# MUX_Adapter.net
KiCad netlist of a schematic drawn in EAGLE
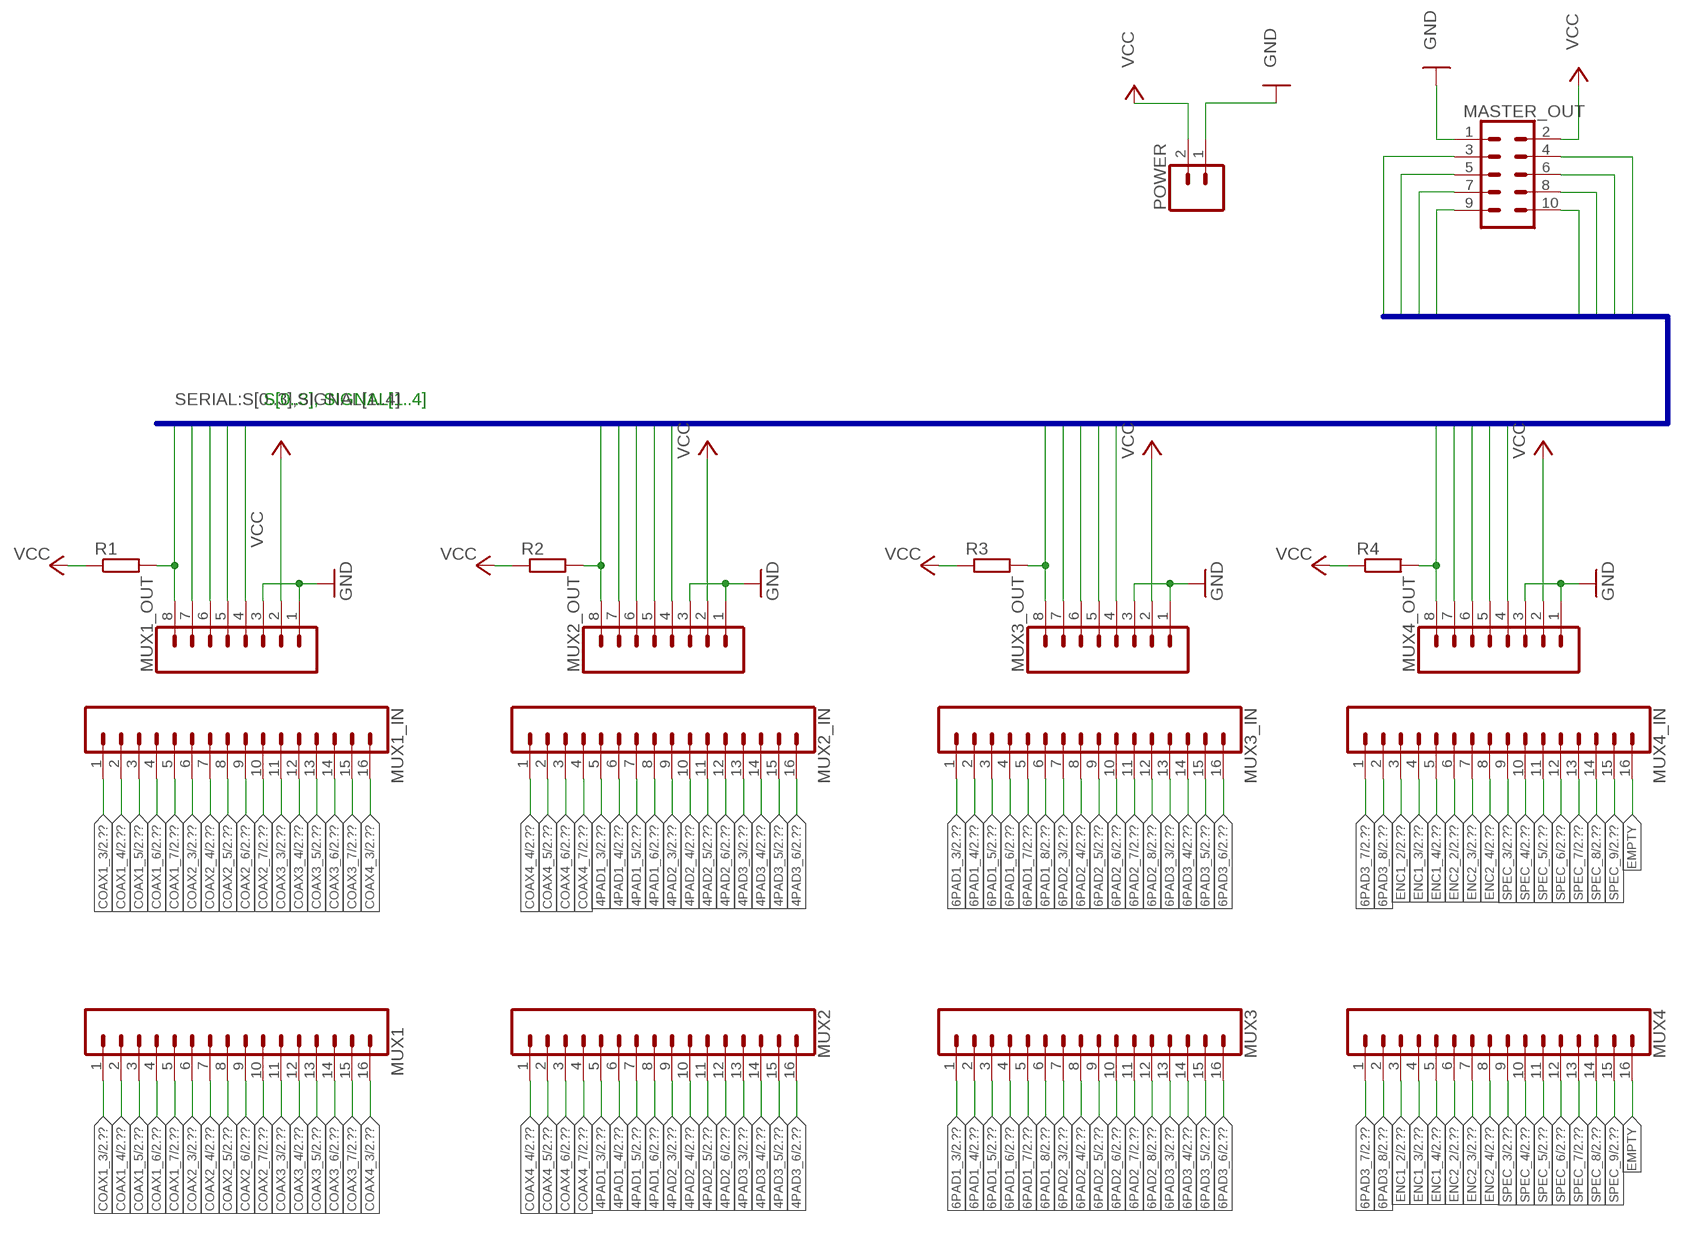
[diagram p0: schematic, sheet 1]
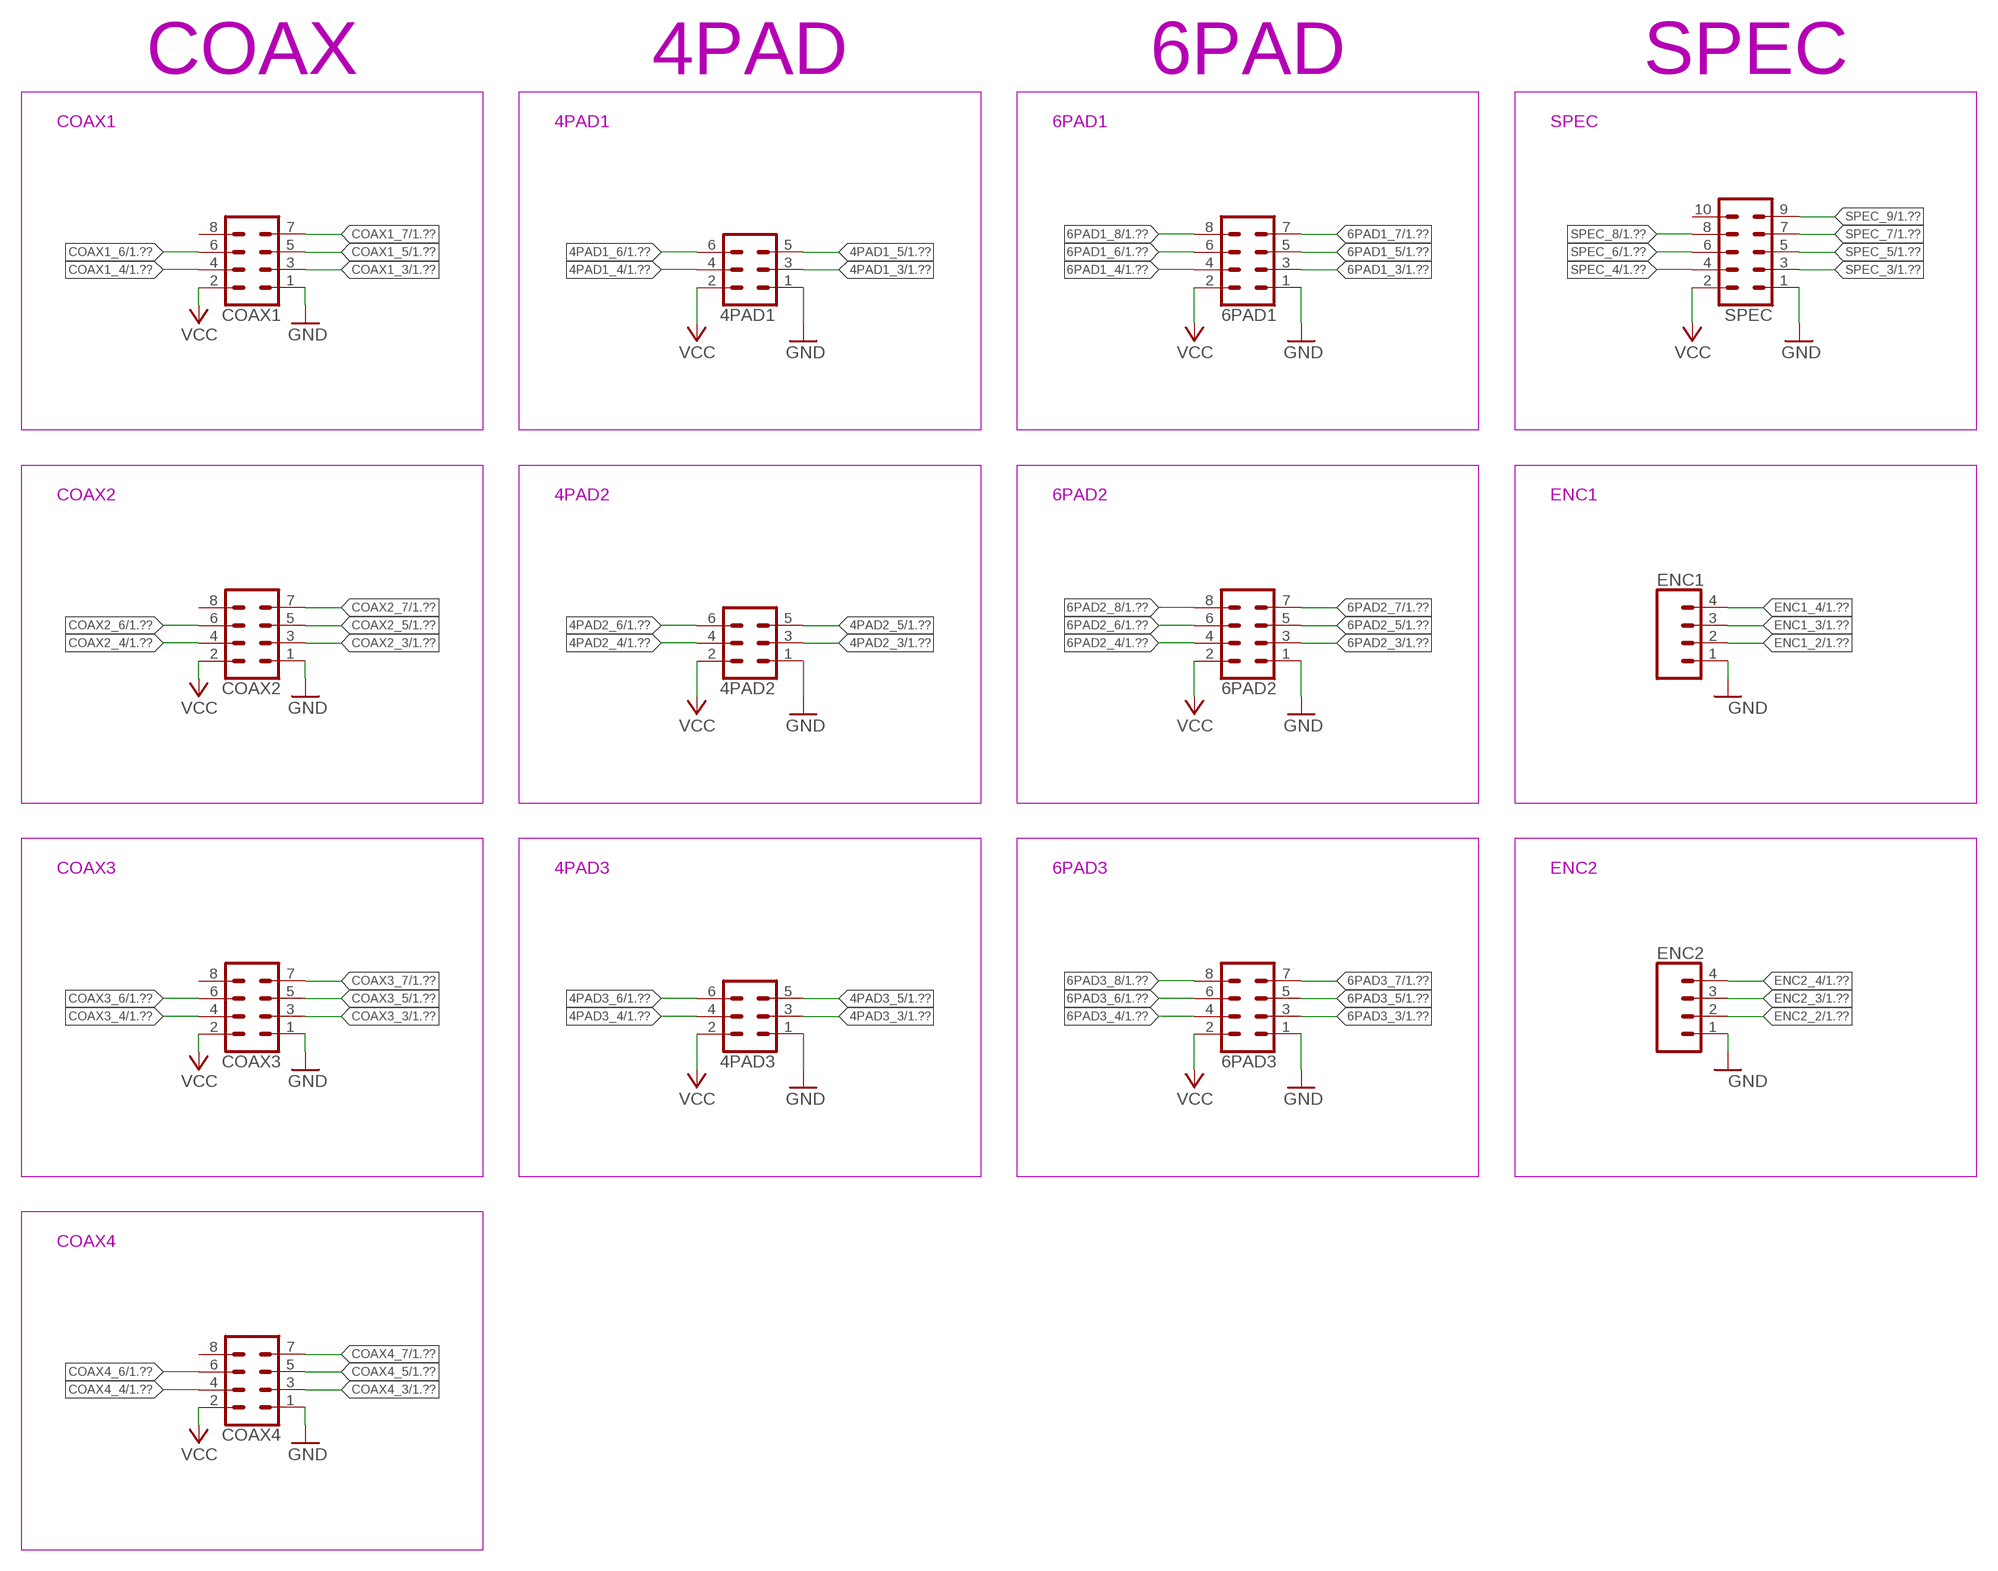
[diagram p1: schematic, sheet 2]

(export (version "E")
  (design (tool "Eeschema 10.0.6"))
  (components
    (comp (ref "4PAD1")
      (value "CONN_03X2NO_SILK")
      (footprint "eagle-import:2X3-NS")
      (libsource (lib "eagle-import") (part "CONN_03X2NO_SILK"))
    )
    (comp (ref "4PAD2")
      (value "CONN_03X2NO_SILK")
      (footprint "eagle-import:2X3-NS")
      (libsource (lib "eagle-import") (part "CONN_03X2NO_SILK"))
    )
    (comp (ref "4PAD3")
      (value "CONN_03X2NO_SILK")
      (footprint "eagle-import:2X3-NS")
      (libsource (lib "eagle-import") (part "CONN_03X2NO_SILK"))
    )
    (comp (ref "6PAD1")
      (value "CONN_04X2")
      (footprint "eagle-import:2X4")
      (libsource (lib "eagle-import") (part "CONN_04X2"))
    )
    (comp (ref "6PAD2")
      (value "CONN_04X2")
      (footprint "eagle-import:2X4")
      (libsource (lib "eagle-import") (part "CONN_04X2"))
    )
    (comp (ref "6PAD3")
      (value "CONN_04X2")
      (footprint "eagle-import:2X4")
      (libsource (lib "eagle-import") (part "CONN_04X2"))
    )
    (comp (ref "COAX1")
      (value "CONN_04X2")
      (footprint "eagle-import:2X4")
      (libsource (lib "eagle-import") (part "CONN_04X2"))
    )
    (comp (ref "COAX2")
      (value "CONN_04X2")
      (footprint "eagle-import:2X4")
      (libsource (lib "eagle-import") (part "CONN_04X2"))
    )
    (comp (ref "COAX3")
      (value "CONN_04X2")
      (footprint "eagle-import:2X4")
      (libsource (lib "eagle-import") (part "CONN_04X2"))
    )
    (comp (ref "COAX4")
      (value "CONN_04X2")
      (footprint "eagle-import:2X4")
      (libsource (lib "eagle-import") (part "CONN_04X2"))
    )
    (comp (ref "ENC1")
      (value "CONN_04PTH")
      (footprint "eagle-import:1X04")
      (libsource (lib "eagle-import") (part "CONN_04PTH"))
    )
    (comp (ref "ENC2")
      (value "CONN_04PTH")
      (footprint "eagle-import:1X04")
      (libsource (lib "eagle-import") (part "CONN_04PTH"))
    )
    (comp (ref "SPEC")
      (value "CONN_05X2PTH")
      (footprint "eagle-import:2X5")
      (libsource (lib "eagle-import") (part "CONN_05X2PTH"))
    )
    (comp (ref "MASTER_OUT")
      (value "CONN_05X2SHD-NS")
      (footprint "eagle-import:2X5-SHROUDED-NS")
      (libsource (lib "eagle-import") (part "CONN_05X2SHD-NS"))
    )
    (comp (ref "MUX1")
      (value "CONN_16")
      (footprint "eagle-import:1X16")
      (libsource (lib "eagle-import") (part "CONN_16"))
    )
    (comp (ref "MUX1_IN")
      (value "CONN_16")
      (footprint "eagle-import:1X16")
      (libsource (lib "eagle-import") (part "CONN_16"))
    )
    (comp (ref "MUX1_OUT")
      (value "CONN_08\"")
      (footprint "eagle-import:1X08")
      (libsource (lib "eagle-import") (part "CONN_08{dblquote}"))
    )
    (comp (ref "MUX2")
      (value "CONN_16")
      (footprint "eagle-import:1X16")
      (libsource (lib "eagle-import") (part "CONN_16"))
    )
    (comp (ref "MUX2_IN")
      (value "CONN_16")
      (footprint "eagle-import:1X16")
      (libsource (lib "eagle-import") (part "CONN_16"))
    )
    (comp (ref "MUX2_OUT")
      (value "CONN_08\"")
      (footprint "eagle-import:1X08")
      (libsource (lib "eagle-import") (part "CONN_08{dblquote}"))
    )
    (comp (ref "MUX3")
      (value "CONN_16")
      (footprint "eagle-import:1X16")
      (libsource (lib "eagle-import") (part "CONN_16"))
    )
    (comp (ref "MUX3_IN")
      (value "CONN_16")
      (footprint "eagle-import:1X16")
      (libsource (lib "eagle-import") (part "CONN_16"))
    )
    (comp (ref "MUX3_OUT")
      (value "CONN_08\"")
      (footprint "eagle-import:1X08")
      (libsource (lib "eagle-import") (part "CONN_08{dblquote}"))
    )
    (comp (ref "MUX4")
      (value "CONN_16")
      (footprint "eagle-import:1X16")
      (libsource (lib "eagle-import") (part "CONN_16"))
    )
    (comp (ref "MUX4_IN")
      (value "CONN_16")
      (footprint "eagle-import:1X16")
      (libsource (lib "eagle-import") (part "CONN_16"))
    )
    (comp (ref "MUX4_OUT")
      (value "CONN_08\"")
      (footprint "eagle-import:1X08")
      (libsource (lib "eagle-import") (part "CONN_08{dblquote}"))
    )
    (comp (ref "POWER")
      (value "CONN_02")
      (footprint "eagle-import:1X02")
      (libsource (lib "eagle-import") (part "CONN_02"))
    )
    (comp (ref "R1")
      (value "R-EU_0207/10")
      (footprint "eagle-import:0207_10")
      (libsource (lib "eagle-import") (part "R-EU_0207/10"))
    )
    (comp (ref "R2")
      (value "R-EU_0207/10")
      (footprint "eagle-import:0207_10")
      (libsource (lib "eagle-import") (part "R-EU_0207/10"))
    )
    (comp (ref "R3")
      (value "R-EU_0207/10")
      (footprint "eagle-import:0207_10")
      (libsource (lib "eagle-import") (part "R-EU_0207/10"))
    )
    (comp (ref "R4")
      (value "R-EU_0207/10")
      (footprint "eagle-import:0207_10")
      (libsource (lib "eagle-import") (part "R-EU_0207/10"))
    )
  )
  (nets
    (net (code "2") (name "4PAD1_3") (class "Default")
      (node (ref "4PAD1") (pin "3") (pinfunction "3_3") (pintype "bidirectional"))
      (node (ref "MUX2") (pin "5") (pinfunction "5_5") (pintype "passive"))
      (node (ref "MUX2_IN") (pin "5") (pinfunction "5_5") (pintype "passive"))
    )
    (net (code "3") (name "4PAD1_4") (class "Default")
      (node (ref "4PAD1") (pin "4") (pinfunction "4_4") (pintype "bidirectional"))
      (node (ref "MUX2") (pin "6") (pinfunction "6_6") (pintype "passive"))
      (node (ref "MUX2_IN") (pin "6") (pinfunction "6_6") (pintype "passive"))
    )
    (net (code "4") (name "4PAD1_5") (class "Default")
      (node (ref "4PAD1") (pin "5") (pinfunction "5_5") (pintype "bidirectional"))
      (node (ref "MUX2") (pin "7") (pinfunction "7_7") (pintype "passive"))
      (node (ref "MUX2_IN") (pin "7") (pinfunction "7_7") (pintype "passive"))
    )
    (net (code "5") (name "4PAD1_6") (class "Default")
      (node (ref "4PAD1") (pin "6") (pinfunction "6_6") (pintype "bidirectional"))
      (node (ref "MUX2") (pin "8") (pinfunction "8_8") (pintype "passive"))
      (node (ref "MUX2_IN") (pin "8") (pinfunction "8_8") (pintype "passive"))
    )
    (net (code "6") (name "4PAD2_3") (class "Default")
      (node (ref "4PAD2") (pin "3") (pinfunction "3_3") (pintype "bidirectional"))
      (node (ref "MUX2") (pin "9") (pinfunction "9_9") (pintype "passive"))
      (node (ref "MUX2_IN") (pin "9") (pinfunction "9_9") (pintype "passive"))
    )
    (net (code "7") (name "4PAD2_4") (class "Default")
      (node (ref "4PAD2") (pin "4") (pinfunction "4_4") (pintype "bidirectional"))
      (node (ref "MUX2") (pin "10") (pinfunction "10_10") (pintype "passive"))
      (node (ref "MUX2_IN") (pin "10") (pinfunction "10_10") (pintype "passive"))
    )
    (net (code "8") (name "4PAD2_5") (class "Default")
      (node (ref "4PAD2") (pin "5") (pinfunction "5_5") (pintype "bidirectional"))
      (node (ref "MUX2") (pin "11") (pinfunction "11_11") (pintype "passive"))
      (node (ref "MUX2_IN") (pin "11") (pinfunction "11_11") (pintype "passive"))
    )
    (net (code "9") (name "4PAD2_6") (class "Default")
      (node (ref "4PAD2") (pin "6") (pinfunction "6_6") (pintype "bidirectional"))
      (node (ref "MUX2") (pin "12") (pinfunction "12_12") (pintype "passive"))
      (node (ref "MUX2_IN") (pin "12") (pinfunction "12_12") (pintype "passive"))
    )
    (net (code "10") (name "4PAD3_3") (class "Default")
      (node (ref "4PAD3") (pin "3") (pinfunction "3_3") (pintype "bidirectional"))
      (node (ref "MUX2") (pin "13") (pinfunction "13_13") (pintype "passive"))
      (node (ref "MUX2_IN") (pin "13") (pinfunction "13_13") (pintype "passive"))
    )
    (net (code "11") (name "4PAD3_4") (class "Default")
      (node (ref "4PAD3") (pin "4") (pinfunction "4_4") (pintype "bidirectional"))
      (node (ref "MUX2") (pin "14") (pinfunction "14_14") (pintype "passive"))
      (node (ref "MUX2_IN") (pin "14") (pinfunction "14_14") (pintype "passive"))
    )
    (net (code "12") (name "4PAD3_5") (class "Default")
      (node (ref "4PAD3") (pin "5") (pinfunction "5_5") (pintype "bidirectional"))
      (node (ref "MUX2") (pin "15") (pinfunction "15_15") (pintype "passive"))
      (node (ref "MUX2_IN") (pin "15") (pinfunction "15_15") (pintype "passive"))
    )
    (net (code "13") (name "4PAD3_6") (class "Default")
      (node (ref "4PAD3") (pin "6") (pinfunction "6_6") (pintype "bidirectional"))
      (node (ref "MUX2") (pin "16") (pinfunction "16_16") (pintype "passive"))
      (node (ref "MUX2_IN") (pin "16") (pinfunction "16_16") (pintype "passive"))
    )
    (net (code "14") (name "6PAD1_3") (class "Default")
      (node (ref "6PAD1") (pin "3") (pinfunction "3_3") (pintype "passive"))
      (node (ref "MUX3") (pin "1") (pinfunction "1_1") (pintype "passive"))
      (node (ref "MUX3_IN") (pin "1") (pinfunction "1_1") (pintype "passive"))
    )
    (net (code "15") (name "6PAD1_4") (class "Default")
      (node (ref "6PAD1") (pin "4") (pinfunction "4_4") (pintype "passive"))
      (node (ref "MUX3") (pin "2") (pinfunction "2_2") (pintype "passive"))
      (node (ref "MUX3_IN") (pin "2") (pinfunction "2_2") (pintype "passive"))
    )
    (net (code "16") (name "6PAD1_5") (class "Default")
      (node (ref "6PAD1") (pin "5") (pinfunction "5_5") (pintype "passive"))
      (node (ref "MUX3") (pin "3") (pinfunction "3_3") (pintype "passive"))
      (node (ref "MUX3_IN") (pin "3") (pinfunction "3_3") (pintype "passive"))
    )
    (net (code "17") (name "6PAD1_6") (class "Default")
      (node (ref "6PAD1") (pin "6") (pinfunction "6_6") (pintype "passive"))
      (node (ref "MUX3") (pin "4") (pinfunction "4_4") (pintype "passive"))
      (node (ref "MUX3_IN") (pin "4") (pinfunction "4_4") (pintype "passive"))
    )
    (net (code "18") (name "6PAD1_7") (class "Default")
      (node (ref "6PAD1") (pin "7") (pinfunction "7_7") (pintype "passive"))
      (node (ref "MUX3") (pin "5") (pinfunction "5_5") (pintype "passive"))
      (node (ref "MUX3_IN") (pin "5") (pinfunction "5_5") (pintype "passive"))
    )
    (net (code "19") (name "6PAD1_8") (class "Default")
      (node (ref "6PAD1") (pin "8") (pinfunction "8_8") (pintype "passive"))
      (node (ref "MUX3") (pin "6") (pinfunction "6_6") (pintype "passive"))
      (node (ref "MUX3_IN") (pin "6") (pinfunction "6_6") (pintype "passive"))
    )
    (net (code "20") (name "6PAD2_3") (class "Default")
      (node (ref "6PAD2") (pin "3") (pinfunction "3_3") (pintype "passive"))
      (node (ref "MUX3") (pin "7") (pinfunction "7_7") (pintype "passive"))
      (node (ref "MUX3_IN") (pin "7") (pinfunction "7_7") (pintype "passive"))
    )
    (net (code "21") (name "6PAD2_4") (class "Default")
      (node (ref "6PAD2") (pin "4") (pinfunction "4_4") (pintype "passive"))
      (node (ref "MUX3") (pin "8") (pinfunction "8_8") (pintype "passive"))
      (node (ref "MUX3_IN") (pin "8") (pinfunction "8_8") (pintype "passive"))
    )
    (net (code "22") (name "6PAD2_5") (class "Default")
      (node (ref "6PAD2") (pin "5") (pinfunction "5_5") (pintype "passive"))
      (node (ref "MUX3") (pin "9") (pinfunction "9_9") (pintype "passive"))
      (node (ref "MUX3_IN") (pin "9") (pinfunction "9_9") (pintype "passive"))
    )
    (net (code "23") (name "6PAD2_6") (class "Default")
      (node (ref "6PAD2") (pin "6") (pinfunction "6_6") (pintype "passive"))
      (node (ref "MUX3") (pin "10") (pinfunction "10_10") (pintype "passive"))
      (node (ref "MUX3_IN") (pin "10") (pinfunction "10_10") (pintype "passive"))
    )
    (net (code "24") (name "6PAD2_7") (class "Default")
      (node (ref "6PAD2") (pin "7") (pinfunction "7_7") (pintype "passive"))
      (node (ref "MUX3") (pin "11") (pinfunction "11_11") (pintype "passive"))
      (node (ref "MUX3_IN") (pin "11") (pinfunction "11_11") (pintype "passive"))
    )
    (net (code "25") (name "6PAD2_8") (class "Default")
      (node (ref "6PAD2") (pin "8") (pinfunction "8_8") (pintype "passive"))
      (node (ref "MUX3") (pin "12") (pinfunction "12_12") (pintype "passive"))
      (node (ref "MUX3_IN") (pin "12") (pinfunction "12_12") (pintype "passive"))
    )
    (net (code "26") (name "6PAD3_3") (class "Default")
      (node (ref "6PAD3") (pin "3") (pinfunction "3_3") (pintype "passive"))
      (node (ref "MUX3") (pin "13") (pinfunction "13_13") (pintype "passive"))
      (node (ref "MUX3_IN") (pin "13") (pinfunction "13_13") (pintype "passive"))
    )
    (net (code "27") (name "6PAD3_4") (class "Default")
      (node (ref "6PAD3") (pin "4") (pinfunction "4_4") (pintype "passive"))
      (node (ref "MUX3") (pin "14") (pinfunction "14_14") (pintype "passive"))
      (node (ref "MUX3_IN") (pin "14") (pinfunction "14_14") (pintype "passive"))
    )
    (net (code "28") (name "6PAD3_5") (class "Default")
      (node (ref "6PAD3") (pin "5") (pinfunction "5_5") (pintype "passive"))
      (node (ref "MUX3") (pin "15") (pinfunction "15_15") (pintype "passive"))
      (node (ref "MUX3_IN") (pin "15") (pinfunction "15_15") (pintype "passive"))
    )
    (net (code "29") (name "6PAD3_6") (class "Default")
      (node (ref "6PAD3") (pin "6") (pinfunction "6_6") (pintype "passive"))
      (node (ref "MUX3") (pin "16") (pinfunction "16_16") (pintype "passive"))
      (node (ref "MUX3_IN") (pin "16") (pinfunction "16_16") (pintype "passive"))
    )
    (net (code "30") (name "6PAD3_7") (class "Default")
      (node (ref "6PAD3") (pin "7") (pinfunction "7_7") (pintype "passive"))
      (node (ref "MUX4") (pin "1") (pinfunction "1_1") (pintype "passive"))
      (node (ref "MUX4_IN") (pin "1") (pinfunction "1_1") (pintype "passive"))
    )
    (net (code "31") (name "6PAD3_8") (class "Default")
      (node (ref "6PAD3") (pin "8") (pinfunction "8_8") (pintype "passive"))
      (node (ref "MUX4") (pin "2") (pinfunction "2_2") (pintype "passive"))
      (node (ref "MUX4_IN") (pin "2") (pinfunction "2_2") (pintype "passive"))
    )
    (net (code "32") (name "COAX1_3") (class "Default")
      (node (ref "COAX1") (pin "3") (pinfunction "3_3") (pintype "passive"))
      (node (ref "MUX1") (pin "1") (pinfunction "1_1") (pintype "passive"))
      (node (ref "MUX1_IN") (pin "1") (pinfunction "1_1") (pintype "passive"))
    )
    (net (code "33") (name "COAX1_4") (class "Default")
      (node (ref "COAX1") (pin "4") (pinfunction "4_4") (pintype "passive"))
      (node (ref "MUX1") (pin "2") (pinfunction "2_2") (pintype "passive"))
      (node (ref "MUX1_IN") (pin "2") (pinfunction "2_2") (pintype "passive"))
    )
    (net (code "34") (name "COAX1_5") (class "Default")
      (node (ref "COAX1") (pin "5") (pinfunction "5_5") (pintype "passive"))
      (node (ref "MUX1") (pin "3") (pinfunction "3_3") (pintype "passive"))
      (node (ref "MUX1_IN") (pin "3") (pinfunction "3_3") (pintype "passive"))
    )
    (net (code "35") (name "COAX1_6") (class "Default")
      (node (ref "COAX1") (pin "6") (pinfunction "6_6") (pintype "passive"))
      (node (ref "MUX1") (pin "4") (pinfunction "4_4") (pintype "passive"))
      (node (ref "MUX1_IN") (pin "4") (pinfunction "4_4") (pintype "passive"))
    )
    (net (code "36") (name "COAX1_7") (class "Default")
      (node (ref "COAX1") (pin "7") (pinfunction "7_7") (pintype "passive"))
      (node (ref "MUX1") (pin "5") (pinfunction "5_5") (pintype "passive"))
      (node (ref "MUX1_IN") (pin "5") (pinfunction "5_5") (pintype "passive"))
    )
    (net (code "37") (name "COAX2_3") (class "Default")
      (node (ref "COAX2") (pin "3") (pinfunction "3_3") (pintype "passive"))
      (node (ref "MUX1") (pin "6") (pinfunction "6_6") (pintype "passive"))
      (node (ref "MUX1_IN") (pin "6") (pinfunction "6_6") (pintype "passive"))
    )
    (net (code "38") (name "COAX2_4") (class "Default")
      (node (ref "COAX2") (pin "4") (pinfunction "4_4") (pintype "passive"))
      (node (ref "MUX1") (pin "7") (pinfunction "7_7") (pintype "passive"))
      (node (ref "MUX1_IN") (pin "7") (pinfunction "7_7") (pintype "passive"))
    )
    (net (code "39") (name "COAX2_5") (class "Default")
      (node (ref "COAX2") (pin "5") (pinfunction "5_5") (pintype "passive"))
      (node (ref "MUX1") (pin "8") (pinfunction "8_8") (pintype "passive"))
      (node (ref "MUX1_IN") (pin "8") (pinfunction "8_8") (pintype "passive"))
    )
    (net (code "40") (name "COAX2_6") (class "Default")
      (node (ref "COAX2") (pin "6") (pinfunction "6_6") (pintype "passive"))
      (node (ref "MUX1") (pin "9") (pinfunction "9_9") (pintype "passive"))
      (node (ref "MUX1_IN") (pin "9") (pinfunction "9_9") (pintype "passive"))
    )
    (net (code "41") (name "COAX2_7") (class "Default")
      (node (ref "COAX2") (pin "7") (pinfunction "7_7") (pintype "passive"))
      (node (ref "MUX1") (pin "10") (pinfunction "10_10") (pintype "passive"))
      (node (ref "MUX1_IN") (pin "10") (pinfunction "10_10") (pintype "passive"))
    )
    (net (code "42") (name "COAX3_3") (class "Default")
      (node (ref "COAX3") (pin "3") (pinfunction "3_3") (pintype "passive"))
      (node (ref "MUX1") (pin "11") (pinfunction "11_11") (pintype "passive"))
      (node (ref "MUX1_IN") (pin "11") (pinfunction "11_11") (pintype "passive"))
    )
    (net (code "43") (name "COAX3_4") (class "Default")
      (node (ref "COAX3") (pin "4") (pinfunction "4_4") (pintype "passive"))
      (node (ref "MUX1") (pin "12") (pinfunction "12_12") (pintype "passive"))
      (node (ref "MUX1_IN") (pin "12") (pinfunction "12_12") (pintype "passive"))
    )
    (net (code "44") (name "COAX3_5") (class "Default")
      (node (ref "COAX3") (pin "5") (pinfunction "5_5") (pintype "passive"))
      (node (ref "MUX1") (pin "13") (pinfunction "13_13") (pintype "passive"))
      (node (ref "MUX1_IN") (pin "13") (pinfunction "13_13") (pintype "passive"))
    )
    (net (code "45") (name "COAX3_6") (class "Default")
      (node (ref "COAX3") (pin "6") (pinfunction "6_6") (pintype "passive"))
      (node (ref "MUX1") (pin "14") (pinfunction "14_14") (pintype "passive"))
      (node (ref "MUX1_IN") (pin "14") (pinfunction "14_14") (pintype "passive"))
    )
    (net (code "46") (name "COAX3_7") (class "Default")
      (node (ref "COAX3") (pin "7") (pinfunction "7_7") (pintype "passive"))
      (node (ref "MUX1") (pin "15") (pinfunction "15_15") (pintype "passive"))
      (node (ref "MUX1_IN") (pin "15") (pinfunction "15_15") (pintype "passive"))
    )
    (net (code "47") (name "COAX4_3") (class "Default")
      (node (ref "COAX4") (pin "3") (pinfunction "3_3") (pintype "passive"))
      (node (ref "MUX1") (pin "16") (pinfunction "16_16") (pintype "passive"))
      (node (ref "MUX1_IN") (pin "16") (pinfunction "16_16") (pintype "passive"))
    )
    (net (code "48") (name "COAX4_4") (class "Default")
      (node (ref "COAX4") (pin "4") (pinfunction "4_4") (pintype "passive"))
      (node (ref "MUX2") (pin "1") (pinfunction "1_1") (pintype "passive"))
      (node (ref "MUX2_IN") (pin "1") (pinfunction "1_1") (pintype "passive"))
    )
    (net (code "49") (name "COAX4_5") (class "Default")
      (node (ref "COAX4") (pin "5") (pinfunction "5_5") (pintype "passive"))
      (node (ref "MUX2") (pin "2") (pinfunction "2_2") (pintype "passive"))
      (node (ref "MUX2_IN") (pin "2") (pinfunction "2_2") (pintype "passive"))
    )
    (net (code "50") (name "COAX4_6") (class "Default")
      (node (ref "COAX4") (pin "6") (pinfunction "6_6") (pintype "passive"))
      (node (ref "MUX2") (pin "3") (pinfunction "3_3") (pintype "passive"))
      (node (ref "MUX2_IN") (pin "3") (pinfunction "3_3") (pintype "passive"))
    )
    (net (code "51") (name "COAX4_7") (class "Default")
      (node (ref "COAX4") (pin "7") (pinfunction "7_7") (pintype "passive"))
      (node (ref "MUX2") (pin "4") (pinfunction "4_4") (pintype "passive"))
      (node (ref "MUX2_IN") (pin "4") (pinfunction "4_4") (pintype "passive"))
    )
    (net (code "52") (name "EMPTY") (class "Default")
      (node (ref "MUX4") (pin "16") (pinfunction "16_16") (pintype "passive"))
      (node (ref "MUX4_IN") (pin "16") (pinfunction "16_16") (pintype "passive"))
    )
    (net (code "53") (name "ENC1_2") (class "Default")
      (node (ref "ENC1") (pin "2") (pinfunction "2_2") (pintype "passive"))
      (node (ref "MUX4") (pin "3") (pinfunction "3_3") (pintype "passive"))
      (node (ref "MUX4_IN") (pin "3") (pinfunction "3_3") (pintype "passive"))
    )
    (net (code "54") (name "ENC1_3") (class "Default")
      (node (ref "ENC1") (pin "3") (pinfunction "3_3") (pintype "passive"))
      (node (ref "MUX4") (pin "4") (pinfunction "4_4") (pintype "passive"))
      (node (ref "MUX4_IN") (pin "4") (pinfunction "4_4") (pintype "passive"))
    )
    (net (code "55") (name "ENC1_4") (class "Default")
      (node (ref "ENC1") (pin "4") (pinfunction "4_4") (pintype "passive"))
      (node (ref "MUX4") (pin "5") (pinfunction "5_5") (pintype "passive"))
      (node (ref "MUX4_IN") (pin "5") (pinfunction "5_5") (pintype "passive"))
    )
    (net (code "56") (name "ENC2_2") (class "Default")
      (node (ref "ENC2") (pin "2") (pinfunction "2_2") (pintype "passive"))
      (node (ref "MUX4") (pin "6") (pinfunction "6_6") (pintype "passive"))
      (node (ref "MUX4_IN") (pin "6") (pinfunction "6_6") (pintype "passive"))
    )
    (net (code "57") (name "ENC2_3") (class "Default")
      (node (ref "ENC2") (pin "3") (pinfunction "3_3") (pintype "passive"))
      (node (ref "MUX4") (pin "7") (pinfunction "7_7") (pintype "passive"))
      (node (ref "MUX4_IN") (pin "7") (pinfunction "7_7") (pintype "passive"))
    )
    (net (code "58") (name "ENC2_4") (class "Default")
      (node (ref "ENC2") (pin "4") (pinfunction "4_4") (pintype "passive"))
      (node (ref "MUX4") (pin "8") (pinfunction "8_8") (pintype "passive"))
      (node (ref "MUX4_IN") (pin "8") (pinfunction "8_8") (pintype "passive"))
    )
    (net (code "59") (name "GND") (class "Default")
      (node (ref "4PAD1") (pin "1") (pinfunction "1_1") (pintype "bidirectional"))
      (node (ref "4PAD2") (pin "1") (pinfunction "1_1") (pintype "bidirectional"))
      (node (ref "4PAD3") (pin "1") (pinfunction "1_1") (pintype "bidirectional"))
      (node (ref "6PAD1") (pin "1") (pinfunction "1_1") (pintype "passive"))
      (node (ref "6PAD2") (pin "1") (pinfunction "1_1") (pintype "passive"))
      (node (ref "6PAD3") (pin "1") (pinfunction "1_1") (pintype "passive"))
      (node (ref "COAX1") (pin "1") (pinfunction "1_1") (pintype "passive"))
      (node (ref "COAX2") (pin "1") (pinfunction "1_1") (pintype "passive"))
      (node (ref "COAX3") (pin "1") (pinfunction "1_1") (pintype "passive"))
      (node (ref "COAX4") (pin "1") (pinfunction "1_1") (pintype "passive"))
      (node (ref "ENC1") (pin "1") (pinfunction "1_1") (pintype "passive"))
      (node (ref "ENC2") (pin "1") (pinfunction "1_1") (pintype "passive"))
      (node (ref "MASTER_OUT") (pin "1") (pinfunction "1_1") (pintype "passive"))
      (node (ref "MUX1_OUT") (pin "1") (pinfunction "1_1") (pintype "passive"))
      (node (ref "MUX1_OUT") (pin "3") (pinfunction "3_3") (pintype "passive"))
      (node (ref "MUX2_OUT") (pin "1") (pinfunction "1_1") (pintype "passive"))
      (node (ref "MUX2_OUT") (pin "3") (pinfunction "3_3") (pintype "passive"))
      (node (ref "MUX3_OUT") (pin "1") (pinfunction "1_1") (pintype "passive"))
      (node (ref "MUX3_OUT") (pin "3") (pinfunction "3_3") (pintype "passive"))
      (node (ref "MUX4_OUT") (pin "1") (pinfunction "1_1") (pintype "passive"))
      (node (ref "MUX4_OUT") (pin "3") (pinfunction "3_3") (pintype "passive"))
      (node (ref "POWER") (pin "1") (pinfunction "1_1") (pintype "passive"))
      (node (ref "SPEC") (pin "1") (pinfunction "1_1") (pintype "passive"))
    )
    (net (code "60") (name "S0") (class "Default")
      (node (ref "MASTER_OUT") (pin "3") (pinfunction "3_3") (pintype "passive"))
      (node (ref "MUX1_OUT") (pin "4") (pinfunction "4_4") (pintype "passive"))
      (node (ref "MUX2_OUT") (pin "4") (pinfunction "4_4") (pintype "passive"))
      (node (ref "MUX3_OUT") (pin "4") (pinfunction "4_4") (pintype "passive"))
      (node (ref "MUX4_OUT") (pin "4") (pinfunction "4_4") (pintype "passive"))
    )
    (net (code "61") (name "S1") (class "Default")
      (node (ref "MASTER_OUT") (pin "4") (pinfunction "4_4") (pintype "passive"))
      (node (ref "MUX1_OUT") (pin "5") (pinfunction "5_5") (pintype "passive"))
      (node (ref "MUX2_OUT") (pin "5") (pinfunction "5_5") (pintype "passive"))
      (node (ref "MUX3_OUT") (pin "5") (pinfunction "5_5") (pintype "passive"))
      (node (ref "MUX4_OUT") (pin "5") (pinfunction "5_5") (pintype "passive"))
    )
    (net (code "62") (name "S2") (class "Default")
      (node (ref "MASTER_OUT") (pin "5") (pinfunction "5_5") (pintype "passive"))
      (node (ref "MUX1_OUT") (pin "6") (pinfunction "6_6") (pintype "passive"))
      (node (ref "MUX2_OUT") (pin "6") (pinfunction "6_6") (pintype "passive"))
      (node (ref "MUX3_OUT") (pin "6") (pinfunction "6_6") (pintype "passive"))
      (node (ref "MUX4_OUT") (pin "6") (pinfunction "6_6") (pintype "passive"))
    )
    (net (code "63") (name "S3") (class "Default")
      (node (ref "MASTER_OUT") (pin "6") (pinfunction "6_6") (pintype "passive"))
      (node (ref "MUX1_OUT") (pin "7") (pinfunction "7_7") (pintype "passive"))
      (node (ref "MUX2_OUT") (pin "7") (pinfunction "7_7") (pintype "passive"))
      (node (ref "MUX3_OUT") (pin "7") (pinfunction "7_7") (pintype "passive"))
      (node (ref "MUX4_OUT") (pin "7") (pinfunction "7_7") (pintype "passive"))
    )
    (net (code "64") (name "SIGNAL1") (class "Default")
      (node (ref "MASTER_OUT") (pin "7") (pinfunction "7_7") (pintype "passive"))
      (node (ref "MUX4_OUT") (pin "8") (pinfunction "8_8") (pintype "passive"))
      (node (ref "R4") (pin "2") (pinfunction "2_2") (pintype "passive"))
    )
    (net (code "65") (name "SIGNAL2") (class "Default")
      (node (ref "MASTER_OUT") (pin "8") (pinfunction "8_8") (pintype "passive"))
      (node (ref "MUX3_OUT") (pin "8") (pinfunction "8_8") (pintype "passive"))
      (node (ref "R3") (pin "2") (pinfunction "2_2") (pintype "passive"))
    )
    (net (code "66") (name "SIGNAL3") (class "Default")
      (node (ref "MASTER_OUT") (pin "9") (pinfunction "9_9") (pintype "passive"))
      (node (ref "MUX2_OUT") (pin "8") (pinfunction "8_8") (pintype "passive"))
      (node (ref "R2") (pin "2") (pinfunction "2_2") (pintype "passive"))
    )
    (net (code "67") (name "SIGNAL4") (class "Default")
      (node (ref "MASTER_OUT") (pin "10") (pinfunction "10_10") (pintype "passive"))
      (node (ref "MUX1_OUT") (pin "8") (pinfunction "8_8") (pintype "passive"))
      (node (ref "R1") (pin "2") (pinfunction "2_2") (pintype "passive"))
    )
    (net (code "68") (name "SPEC_3") (class "Default")
      (node (ref "MUX4") (pin "9") (pinfunction "9_9") (pintype "passive"))
      (node (ref "MUX4_IN") (pin "9") (pinfunction "9_9") (pintype "passive"))
      (node (ref "SPEC") (pin "3") (pinfunction "3_3") (pintype "passive"))
    )
    (net (code "69") (name "SPEC_4") (class "Default")
      (node (ref "MUX4") (pin "10") (pinfunction "10_10") (pintype "passive"))
      (node (ref "MUX4_IN") (pin "10") (pinfunction "10_10") (pintype "passive"))
      (node (ref "SPEC") (pin "4") (pinfunction "4_4") (pintype "passive"))
    )
    (net (code "70") (name "SPEC_5") (class "Default")
      (node (ref "MUX4") (pin "11") (pinfunction "11_11") (pintype "passive"))
      (node (ref "MUX4_IN") (pin "11") (pinfunction "11_11") (pintype "passive"))
      (node (ref "SPEC") (pin "5") (pinfunction "5_5") (pintype "passive"))
    )
    (net (code "71") (name "SPEC_6") (class "Default")
      (node (ref "MUX4") (pin "12") (pinfunction "12_12") (pintype "passive"))
      (node (ref "MUX4_IN") (pin "12") (pinfunction "12_12") (pintype "passive"))
      (node (ref "SPEC") (pin "6") (pinfunction "6_6") (pintype "passive"))
    )
    (net (code "72") (name "SPEC_7") (class "Default")
      (node (ref "MUX4") (pin "13") (pinfunction "13_13") (pintype "passive"))
      (node (ref "MUX4_IN") (pin "13") (pinfunction "13_13") (pintype "passive"))
      (node (ref "SPEC") (pin "7") (pinfunction "7_7") (pintype "passive"))
    )
    (net (code "73") (name "SPEC_8") (class "Default")
      (node (ref "MUX4") (pin "14") (pinfunction "14_14") (pintype "passive"))
      (node (ref "MUX4_IN") (pin "14") (pinfunction "14_14") (pintype "passive"))
      (node (ref "SPEC") (pin "8") (pinfunction "8_8") (pintype "passive"))
    )
    (net (code "74") (name "SPEC_9") (class "Default")
      (node (ref "MUX4") (pin "15") (pinfunction "15_15") (pintype "passive"))
      (node (ref "MUX4_IN") (pin "15") (pinfunction "15_15") (pintype "passive"))
      (node (ref "SPEC") (pin "9") (pinfunction "9_9") (pintype "passive"))
    )
    (net (code "75") (name "VCC") (class "Default")
      (node (ref "4PAD1") (pin "2") (pinfunction "2_2") (pintype "bidirectional"))
      (node (ref "4PAD2") (pin "2") (pinfunction "2_2") (pintype "bidirectional"))
      (node (ref "4PAD3") (pin "2") (pinfunction "2_2") (pintype "bidirectional"))
      (node (ref "6PAD1") (pin "2") (pinfunction "2_2") (pintype "passive"))
      (node (ref "6PAD2") (pin "2") (pinfunction "2_2") (pintype "passive"))
      (node (ref "6PAD3") (pin "2") (pinfunction "2_2") (pintype "passive"))
      (node (ref "COAX1") (pin "2") (pinfunction "2_2") (pintype "passive"))
      (node (ref "COAX2") (pin "2") (pinfunction "2_2") (pintype "passive"))
      (node (ref "COAX3") (pin "2") (pinfunction "2_2") (pintype "passive"))
      (node (ref "COAX4") (pin "2") (pinfunction "2_2") (pintype "passive"))
      (node (ref "MASTER_OUT") (pin "2") (pinfunction "2_2") (pintype "passive"))
      (node (ref "MUX1_OUT") (pin "2") (pinfunction "2_2") (pintype "passive"))
      (node (ref "MUX2_OUT") (pin "2") (pinfunction "2_2") (pintype "passive"))
      (node (ref "MUX3_OUT") (pin "2") (pinfunction "2_2") (pintype "passive"))
      (node (ref "MUX4_OUT") (pin "2") (pinfunction "2_2") (pintype "passive"))
      (node (ref "POWER") (pin "2") (pinfunction "2_2") (pintype "passive"))
      (node (ref "R1") (pin "1") (pinfunction "1_1") (pintype "passive"))
      (node (ref "R2") (pin "1") (pinfunction "1_1") (pintype "passive"))
      (node (ref "R3") (pin "1") (pinfunction "1_1") (pintype "passive"))
      (node (ref "R4") (pin "1") (pinfunction "1_1") (pintype "passive"))
      (node (ref "SPEC") (pin "2") (pinfunction "2_2") (pintype "passive"))
    )
    (net (code "76") (name "unconnected-(COAX1-Pad8)") (class "Default")
      (node (ref "COAX1") (pin "8") (pinfunction "8_8") (pintype "passive"))
    )
    (net (code "77") (name "unconnected-(COAX2-Pad8)") (class "Default")
      (node (ref "COAX2") (pin "8") (pinfunction "8_8") (pintype "passive"))
    )
    (net (code "78") (name "unconnected-(COAX3-Pad8)") (class "Default")
      (node (ref "COAX3") (pin "8") (pinfunction "8_8") (pintype "passive"))
    )
    (net (code "79") (name "unconnected-(COAX4-Pad8)") (class "Default")
      (node (ref "COAX4") (pin "8") (pinfunction "8_8") (pintype "passive"))
    )
    (net (code "80") (name "unconnected-(SPEC-Pad10)") (class "Default")
      (node (ref "SPEC") (pin "10") (pinfunction "10_10") (pintype "passive"))
    )
  )
)
